# Adafruit_Ultimate_GPS_HAT.net
KiCad netlist of a schematic drawn in EAGLE
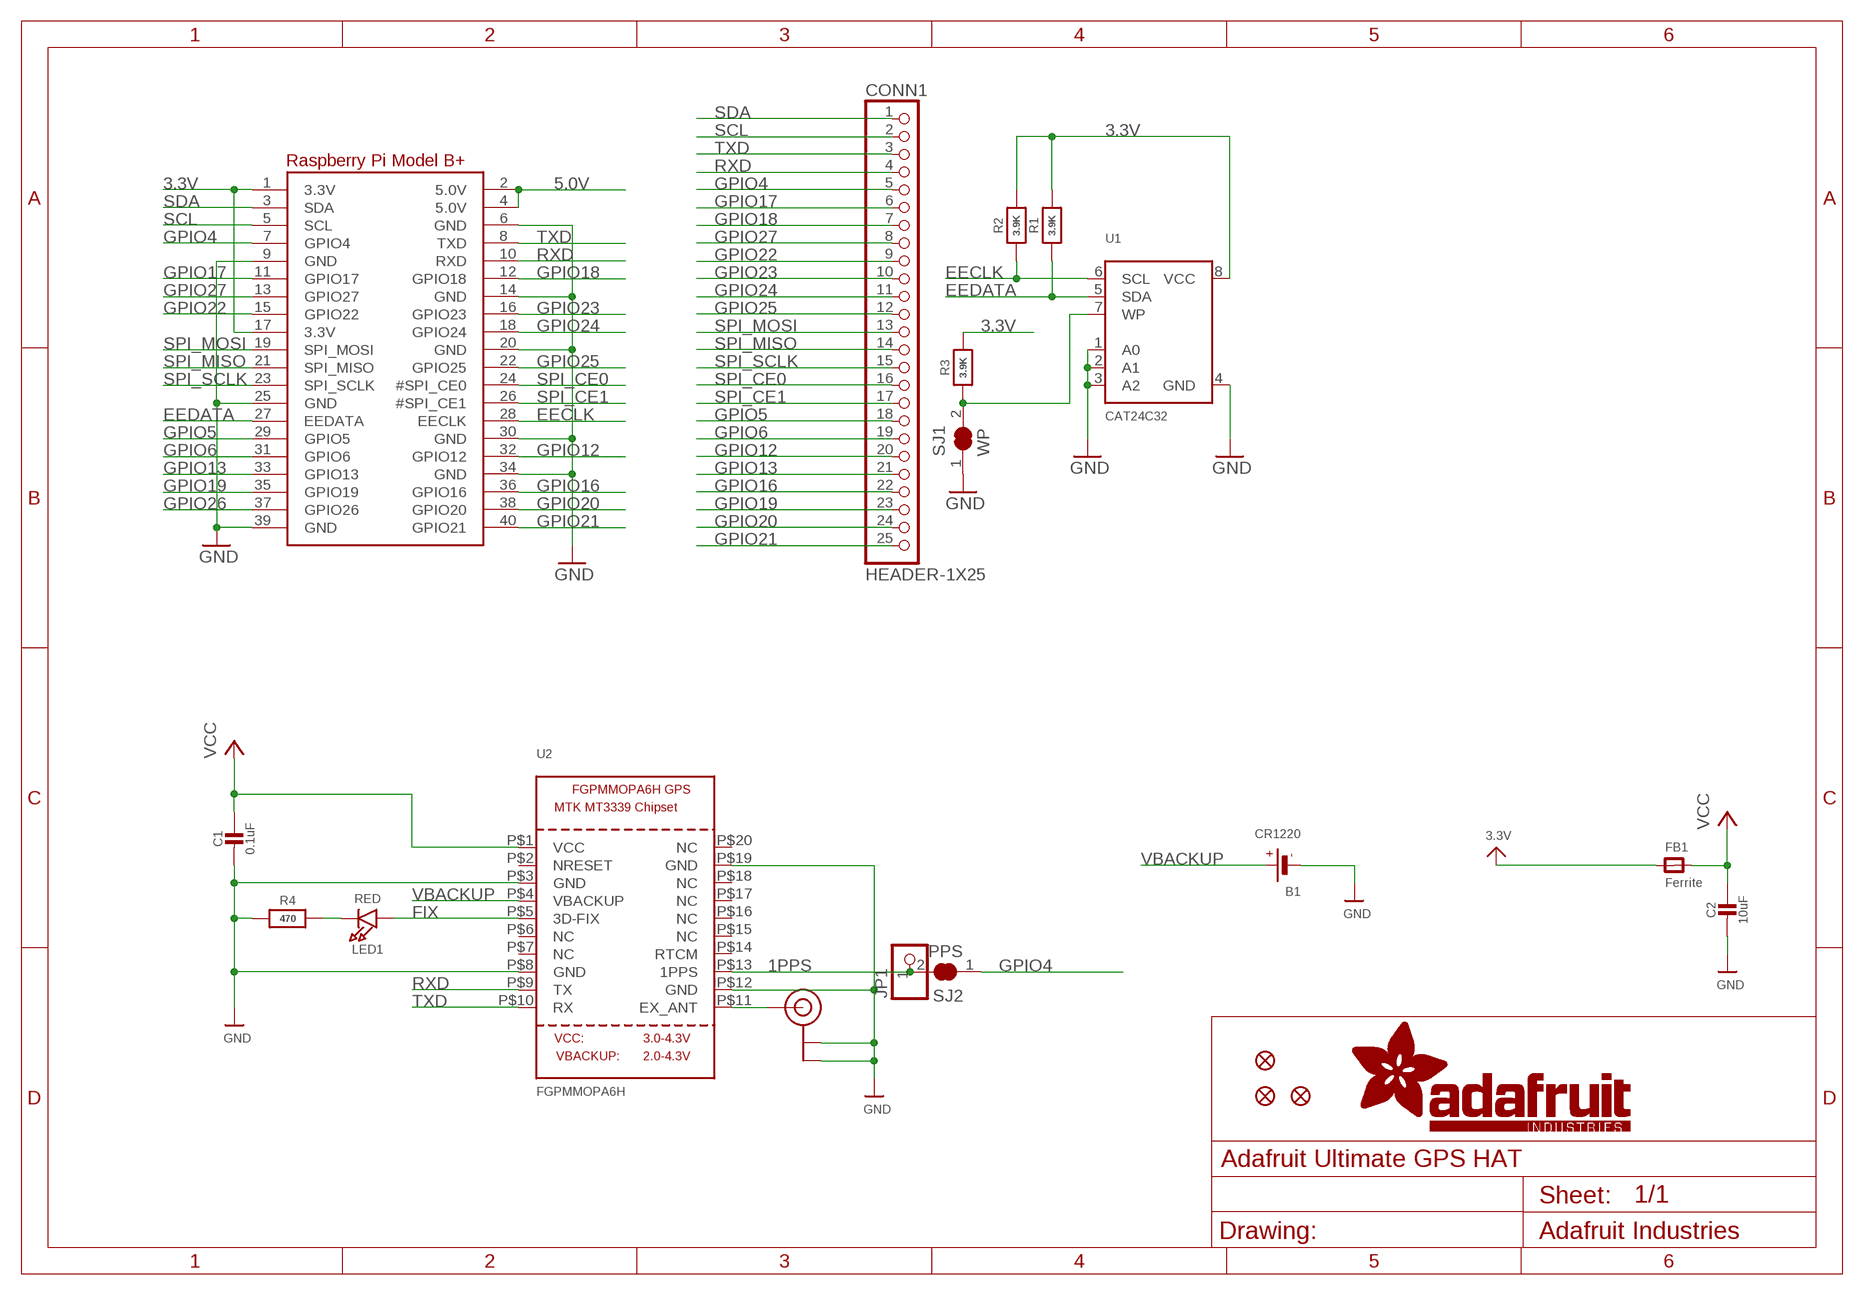
[diagram p0: schematic, sheet 1]

(export (version "E")
  (design (tool "Eeschema 10.0.6"))
  (components
    (comp (ref "B1")
      (value "CR1220")
      (footprint "eagle-import:CR1220")
      (libsource (lib "eagle-import") (part "BATTERYCR1220_SMT"))
    )
    (comp (ref "C1")
      (value "0.1uF")
      (footprint "eagle-import:0805-NO")
      (libsource (lib "eagle-import") (part "CAP_CERAMIC0805-NOOUTLINE"))
    )
    (comp (ref "C2")
      (value "10uF")
      (footprint "eagle-import:0805-NO")
      (libsource (lib "eagle-import") (part "CAP_CERAMIC0805-NOOUTLINE"))
    )
    (comp (ref "CONN1")
      (value "HEADER-1X25")
      (footprint "eagle-import:1X25_ROUND_70MIL")
      (libsource (lib "eagle-import") (part "HEADER-1X25"))
    )
    (comp (ref "FB1")
      (value "Ferrite")
      (footprint "eagle-import:0805")
      (libsource (lib "eagle-import") (part "FERRITE0805"))
    )
    (comp (ref "FID1")
      (value "FIDUCIAL\"\"")
      (footprint "eagle-import:FIDUCIAL_1MM")
      (libsource (lib "eagle-import") (part "FIDUCIAL{dblquote}{dblquote}"))
    )
    (comp (ref "FID2")
      (value "FIDUCIAL\"\"")
      (footprint "eagle-import:FIDUCIAL_1MM")
      (libsource (lib "eagle-import") (part "FIDUCIAL{dblquote}{dblquote}"))
    )
    (comp (ref "FID3")
      (value "FIDUCIAL\"\"")
      (footprint "eagle-import:FIDUCIAL_1MM")
      (libsource (lib "eagle-import") (part "FIDUCIAL{dblquote}{dblquote}"))
    )
    (comp (ref "JP1")
      (value "PINHD-1X1CB")
      (footprint "eagle-import:1X01-CLEANBIG")
      (libsource (lib "eagle-import") (part "PINHD-1X1CB"))
    )
    (comp (ref "LED1")
      (value "RED")
      (footprint "eagle-import:CHIPLED_0805")
      (libsource (lib "eagle-import") (part "LED0805"))
    )
    (comp (ref "R1")
      (value "3.9K")
      (footprint "eagle-import:0805-NO")
      (libsource (lib "eagle-import") (part "RESISTOR0805_NOOUTLINE"))
    )
    (comp (ref "R2")
      (value "3.9K")
      (footprint "eagle-import:0805-NO")
      (libsource (lib "eagle-import") (part "RESISTOR0805_NOOUTLINE"))
    )
    (comp (ref "R3")
      (value "3.9K")
      (footprint "eagle-import:0805-NO")
      (libsource (lib "eagle-import") (part "RESISTOR0805_NOOUTLINE"))
    )
    (comp (ref "R4")
      (value "470")
      (footprint "eagle-import:0805-NO")
      (libsource (lib "eagle-import") (part "RESISTOR0805_NOOUTLINE"))
    )
    (comp (ref "RPI1")
      (value "RASPBERRYPI_BPLUS_HATSLOTS")
      (footprint "eagle-import:PI_HAT_SLOTS")
      (libsource (lib "eagle-import") (part "RASPBERRYPI_BPLUS_HATSLOTS"))
    )
    (comp (ref "SJ1")
      (value "WP")
      (footprint "eagle-import:SOLDERJUMPER_CLOSEDWIRE")
      (libsource (lib "eagle-import") (part "SOLDERJUMPER_CLOSED"))
    )
    (comp (ref "SJ2")
      (value "PPS")
      (footprint "eagle-import:SOLDERJUMPER_CLOSEDWIRE")
      (libsource (lib "eagle-import") (part "SOLDERJUMPER_CLOSED"))
    )
    (comp (ref "U$20")
      (value "U.FL")
      (footprint "eagle-import:U.FL")
      (libsource (lib "eagle-import") (part "U.FL"))
    )
    (comp (ref "U1")
      (value "CAT24C32")
      (footprint "eagle-import:SOIC8_150MIL")
      (libsource (lib "eagle-import") (part "EEPROM_I2C_SOIC8_GENERIC"))
    )
    (comp (ref "U2")
      (value "FGPMMOPA6H")
      (footprint "eagle-import:FGPMMOPA6H")
      (libsource (lib "eagle-import") (part "GPS_FGPMMOPA6H"))
    )
  )
  (nets
    (net (code "1") (name "/1PPS") (class "Default")
      (node (ref "JP1") (pin "1") (pinfunction "1_1") (pintype "passive"))
      (node (ref "SJ2") (pin "2") (pinfunction "2_2") (pintype "passive"))
      (node (ref "U2") (pin "P$13") (pinfunction "1PPS_P$13") (pintype "bidirectional"))
    )
    (net (code "2") (name "/5.0V") (class "Default")
      (node (ref "RPI1") (pin "2") (pinfunction "5.0V_2") (pintype "power_in"))
      (node (ref "RPI1") (pin "4") (pinfunction "5.0V_4") (pintype "power_in"))
    )
    (net (code "3") (name "/EECLK") (class "Default")
      (node (ref "R2") (pin "1") (pinfunction "1_1") (pintype "passive"))
      (node (ref "RPI1") (pin "28") (pinfunction "EECLK_28") (pintype "power_in"))
      (node (ref "U1") (pin "6") (pinfunction "SCL_6") (pintype "input"))
    )
    (net (code "4") (name "/EEDATA") (class "Default")
      (node (ref "R1") (pin "1") (pinfunction "1_1") (pintype "passive"))
      (node (ref "RPI1") (pin "27") (pinfunction "EEDATA_27") (pintype "bidirectional"))
      (node (ref "U1") (pin "5") (pinfunction "SDA_5") (pintype "bidirectional"))
    )
    (net (code "5") (name "/FIX") (class "Default")
      (node (ref "LED1") (pin "A") (pinfunction "A_A") (pintype "passive"))
      (node (ref "U2") (pin "P$5") (pinfunction "3D-FIX_P$5") (pintype "bidirectional"))
    )
    (net (code "6") (name "/GPIO4") (class "Default")
      (node (ref "CONN1") (pin "5") (pinfunction "5_5") (pintype "passive"))
      (node (ref "RPI1") (pin "7") (pinfunction "GPIO4_7") (pintype "bidirectional"))
      (node (ref "SJ2") (pin "1") (pinfunction "1_1") (pintype "passive"))
    )
    (net (code "7") (name "/GPIO5") (class "Default")
      (node (ref "CONN1") (pin "18") (pinfunction "18_18") (pintype "passive"))
      (node (ref "RPI1") (pin "29") (pinfunction "GPIO5_29") (pintype "bidirectional"))
    )
    (net (code "8") (name "/GPIO6") (class "Default")
      (node (ref "CONN1") (pin "19") (pinfunction "19_19") (pintype "passive"))
      (node (ref "RPI1") (pin "31") (pinfunction "GPIO6_31") (pintype "power_in"))
    )
    (net (code "9") (name "/GPIO12") (class "Default")
      (node (ref "CONN1") (pin "20") (pinfunction "20_20") (pintype "passive"))
      (node (ref "RPI1") (pin "32") (pinfunction "GPIO12_32") (pintype "bidirectional"))
    )
    (net (code "10") (name "/GPIO13") (class "Default")
      (node (ref "CONN1") (pin "21") (pinfunction "21_21") (pintype "passive"))
      (node (ref "RPI1") (pin "33") (pinfunction "GPIO13_33") (pintype "bidirectional"))
    )
    (net (code "11") (name "/GPIO16") (class "Default")
      (node (ref "CONN1") (pin "22") (pinfunction "22_22") (pintype "passive"))
      (node (ref "RPI1") (pin "36") (pinfunction "GPIO16_36") (pintype "power_in"))
    )
    (net (code "12") (name "/GPIO17") (class "Default")
      (node (ref "CONN1") (pin "6") (pinfunction "6_6") (pintype "passive"))
      (node (ref "RPI1") (pin "11") (pinfunction "GPIO17_11") (pintype "bidirectional"))
    )
    (net (code "13") (name "/GPIO18") (class "Default")
      (node (ref "CONN1") (pin "7") (pinfunction "7_7") (pintype "passive"))
      (node (ref "RPI1") (pin "12") (pinfunction "GPIO18_12") (pintype "bidirectional"))
    )
    (net (code "14") (name "/GPIO19") (class "Default")
      (node (ref "CONN1") (pin "23") (pinfunction "23_23") (pintype "passive"))
      (node (ref "RPI1") (pin "35") (pinfunction "GPIO19_35") (pintype "bidirectional"))
    )
    (net (code "15") (name "/GPIO20") (class "Default")
      (node (ref "CONN1") (pin "24") (pinfunction "24_24") (pintype "passive"))
      (node (ref "RPI1") (pin "38") (pinfunction "GPIO20_38") (pintype "bidirectional"))
    )
    (net (code "16") (name "/GPIO21") (class "Default")
      (node (ref "CONN1") (pin "25") (pinfunction "25_25") (pintype "passive"))
      (node (ref "RPI1") (pin "40") (pinfunction "GPIO21_40") (pintype "bidirectional"))
    )
    (net (code "17") (name "/GPIO22") (class "Default")
      (node (ref "CONN1") (pin "9") (pinfunction "9_9") (pintype "passive"))
      (node (ref "RPI1") (pin "15") (pinfunction "GPIO22_15") (pintype "bidirectional"))
    )
    (net (code "18") (name "/GPIO23") (class "Default")
      (node (ref "CONN1") (pin "10") (pinfunction "10_10") (pintype "passive"))
      (node (ref "RPI1") (pin "16") (pinfunction "GPIO23_16") (pintype "bidirectional"))
    )
    (net (code "19") (name "/GPIO24") (class "Default")
      (node (ref "CONN1") (pin "11") (pinfunction "11_11") (pintype "passive"))
      (node (ref "RPI1") (pin "18") (pinfunction "GPIO24_18") (pintype "bidirectional"))
    )
    (net (code "20") (name "/GPIO25") (class "Default")
      (node (ref "CONN1") (pin "12") (pinfunction "12_12") (pintype "passive"))
      (node (ref "RPI1") (pin "22") (pinfunction "GPIO25_22") (pintype "bidirectional"))
    )
    (net (code "21") (name "/GPIO26") (class "Default")
      (node (ref "RPI1") (pin "37") (pinfunction "GPIO26_37") (pintype "bidirectional"))
    )
    (net (code "22") (name "/GPIO27") (class "Default")
      (node (ref "CONN1") (pin "8") (pinfunction "8_8") (pintype "passive"))
      (node (ref "RPI1") (pin "13") (pinfunction "GPIO27_13") (pintype "bidirectional"))
    )
    (net (code "23") (name "/RXD") (class "Default")
      (node (ref "CONN1") (pin "4") (pinfunction "4_4") (pintype "passive"))
      (node (ref "RPI1") (pin "10") (pinfunction "RXD_10") (pintype "bidirectional"))
      (node (ref "U2") (pin "P$9") (pinfunction "TX_P$9") (pintype "bidirectional"))
    )
    (net (code "24") (name "/SCL") (class "Default")
      (node (ref "CONN1") (pin "2") (pinfunction "2_2") (pintype "passive"))
      (node (ref "RPI1") (pin "5") (pinfunction "SCL_5") (pintype "bidirectional"))
    )
    (net (code "25") (name "/SDA") (class "Default")
      (node (ref "CONN1") (pin "1") (pinfunction "1_1") (pintype "passive"))
      (node (ref "RPI1") (pin "3") (pinfunction "SDA_3") (pintype "bidirectional"))
    )
    (net (code "26") (name "/SPI_CE0") (class "Default")
      (node (ref "CONN1") (pin "16") (pinfunction "16_16") (pintype "passive"))
      (node (ref "RPI1") (pin "24") (pinfunction "#SPI_CE0_24") (pintype "bidirectional"))
    )
    (net (code "27") (name "/SPI_CE1") (class "Default")
      (node (ref "CONN1") (pin "17") (pinfunction "17_17") (pintype "passive"))
      (node (ref "RPI1") (pin "26") (pinfunction "#SPI_CE1_26") (pintype "bidirectional"))
    )
    (net (code "28") (name "/SPI_MISO") (class "Default")
      (node (ref "CONN1") (pin "14") (pinfunction "14_14") (pintype "passive"))
      (node (ref "RPI1") (pin "21") (pinfunction "SPI_MISO_21") (pintype "bidirectional"))
    )
    (net (code "29") (name "/SPI_MOSI") (class "Default")
      (node (ref "CONN1") (pin "13") (pinfunction "13_13") (pintype "passive"))
      (node (ref "RPI1") (pin "19") (pinfunction "SPI_MOSI_19") (pintype "bidirectional"))
    )
    (net (code "30") (name "/SPI_SCLK") (class "Default")
      (node (ref "CONN1") (pin "15") (pinfunction "15_15") (pintype "passive"))
      (node (ref "RPI1") (pin "23") (pinfunction "SPI_SCLK_23") (pintype "bidirectional"))
    )
    (net (code "31") (name "/TXD") (class "Default")
      (node (ref "CONN1") (pin "3") (pinfunction "3_3") (pintype "passive"))
      (node (ref "RPI1") (pin "8") (pinfunction "TXD_8") (pintype "output"))
      (node (ref "U2") (pin "P$10") (pinfunction "RX_P$10") (pintype "bidirectional"))
    )
    (net (code "32") (name "/VBACKUP") (class "Default")
      (node (ref "B1") (pin "+$1") (pinfunction "+_+$1") (pintype "passive"))
      (node (ref "U2") (pin "P$4") (pinfunction "VBACKUP_P$4") (pintype "bidirectional"))
    )
    (net (code "33") (name "3.3V") (class "Default")
      (node (ref "FB1") (pin "1") (pinfunction "P$1_1") (pintype "passive"))
      (node (ref "R1") (pin "2") (pinfunction "2_2") (pintype "passive"))
      (node (ref "R2") (pin "2") (pinfunction "2_2") (pintype "passive"))
      (node (ref "R3") (pin "2") (pinfunction "2_2") (pintype "passive"))
      (node (ref "RPI1") (pin "1") (pinfunction "3.3V_1") (pintype "power_in"))
      (node (ref "RPI1") (pin "17") (pinfunction "3.3V_17") (pintype "power_in"))
      (node (ref "U1") (pin "8") (pinfunction "VCC_8") (pintype "power_in"))
    )
    (net (code "34") (name "GND") (class "Default")
      (node (ref "B1") (pin "-") (pinfunction "-_-") (pintype "passive"))
      (node (ref "C1") (pin "2") (pinfunction "2_2") (pintype "passive"))
      (node (ref "C2") (pin "2") (pinfunction "2_2") (pintype "passive"))
      (node (ref "R4") (pin "1") (pinfunction "1_1") (pintype "passive"))
      (node (ref "RPI1") (pin "14") (pinfunction "GND_14") (pintype "power_in"))
      (node (ref "RPI1") (pin "20") (pinfunction "GND_20") (pintype "power_in"))
      (node (ref "RPI1") (pin "25") (pinfunction "GND_25") (pintype "power_in"))
      (node (ref "RPI1") (pin "30") (pinfunction "GND_30") (pintype "bidirectional"))
      (node (ref "RPI1") (pin "34") (pinfunction "GND_34") (pintype "bidirectional"))
      (node (ref "RPI1") (pin "39") (pinfunction "GND_39") (pintype "power_in"))
      (node (ref "RPI1") (pin "6") (pinfunction "GND_6") (pintype "power_in"))
      (node (ref "RPI1") (pin "9") (pinfunction "GND_9") (pintype "power_in"))
      (node (ref "SJ1") (pin "1") (pinfunction "1_1") (pintype "passive"))
      (node (ref "U$20") (pin "P$1") (pinfunction "GND_P$1") (pintype "bidirectional"))
      (node (ref "U$20") (pin "P$2") (pinfunction "GND_P$2") (pintype "bidirectional"))
      (node (ref "U1") (pin "1") (pinfunction "A0_1") (pintype "input"))
      (node (ref "U1") (pin "2") (pinfunction "A1_2") (pintype "input"))
      (node (ref "U1") (pin "3") (pinfunction "A2_3") (pintype "input"))
      (node (ref "U1") (pin "4") (pinfunction "GND_4") (pintype "power_in"))
      (node (ref "U2") (pin "P$12") (pinfunction "GND_P$12") (pintype "bidirectional"))
      (node (ref "U2") (pin "P$19") (pinfunction "GND_P$19") (pintype "bidirectional"))
      (node (ref "U2") (pin "P$3") (pinfunction "GND_P$3") (pintype "bidirectional"))
      (node (ref "U2") (pin "P$8") (pinfunction "GND_P$8") (pintype "bidirectional"))
    )
    (net (code "35") (name "Net-(LED1-PadC)") (class "Default")
      (node (ref "LED1") (pin "C") (pinfunction "C_C") (pintype "passive"))
      (node (ref "R4") (pin "2") (pinfunction "2_2") (pintype "passive"))
    )
    (net (code "36") (name "Net-(U$20-SIGNAL)") (class "Default")
      (node (ref "U$20") (pin "P$3") (pinfunction "SIGNAL_P$3") (pintype "bidirectional"))
      (node (ref "U2") (pin "P$11") (pinfunction "EX_ANT_P$11") (pintype "bidirectional"))
    )
    (net (code "37") (name "Net-(U1-WP)") (class "Default")
      (node (ref "R3") (pin "1") (pinfunction "1_1") (pintype "passive"))
      (node (ref "SJ1") (pin "2") (pinfunction "2_2") (pintype "passive"))
      (node (ref "U1") (pin "7") (pinfunction "WP_7") (pintype "input"))
    )
    (net (code "38") (name "VCC") (class "Default")
      (node (ref "C1") (pin "1") (pinfunction "1_1") (pintype "passive"))
      (node (ref "C2") (pin "1") (pinfunction "1_1") (pintype "passive"))
      (node (ref "FB1") (pin "2") (pinfunction "P$2_2") (pintype "passive"))
      (node (ref "U2") (pin "P$1") (pinfunction "VCC_P$1") (pintype "bidirectional"))
    )
    (net (code "39") (name "unconnected-(U2-NC-PadP$6)") (class "Default")
      (node (ref "U2") (pin "P$6") (pinfunction "NC_P$6") (pintype "bidirectional"))
    )
    (net (code "40") (name "unconnected-(U2-NC-PadP$7)") (class "Default")
      (node (ref "U2") (pin "P$7") (pinfunction "NC_P$7") (pintype "bidirectional"))
    )
    (net (code "41") (name "unconnected-(U2-NC-PadP$15)") (class "Default")
      (node (ref "U2") (pin "P$15") (pinfunction "NC_P$15") (pintype "bidirectional"))
    )
    (net (code "42") (name "unconnected-(U2-NC-PadP$16)") (class "Default")
      (node (ref "U2") (pin "P$16") (pinfunction "NC_P$16") (pintype "bidirectional"))
    )
    (net (code "43") (name "unconnected-(U2-NC-PadP$17)") (class "Default")
      (node (ref "U2") (pin "P$17") (pinfunction "NC_P$17") (pintype "bidirectional"))
    )
    (net (code "44") (name "unconnected-(U2-NC-PadP$18)") (class "Default")
      (node (ref "U2") (pin "P$18") (pinfunction "NC_P$18") (pintype "bidirectional"))
    )
    (net (code "45") (name "unconnected-(U2-NC-PadP$20)") (class "Default")
      (node (ref "U2") (pin "P$20") (pinfunction "NC_P$20") (pintype "bidirectional"))
    )
    (net (code "46") (name "unconnected-(U2-NRESET-PadP$2)") (class "Default")
      (node (ref "U2") (pin "P$2") (pinfunction "NRESET_P$2") (pintype "bidirectional"))
    )
    (net (code "47") (name "unconnected-(U2-RTCM-PadP$14)") (class "Default")
      (node (ref "U2") (pin "P$14") (pinfunction "RTCM_P$14") (pintype "bidirectional"))
    )
  )
)
